# ArmDebuger_6-7_Port.net
KiCad netlist of a schematic drawn in Altium Designer
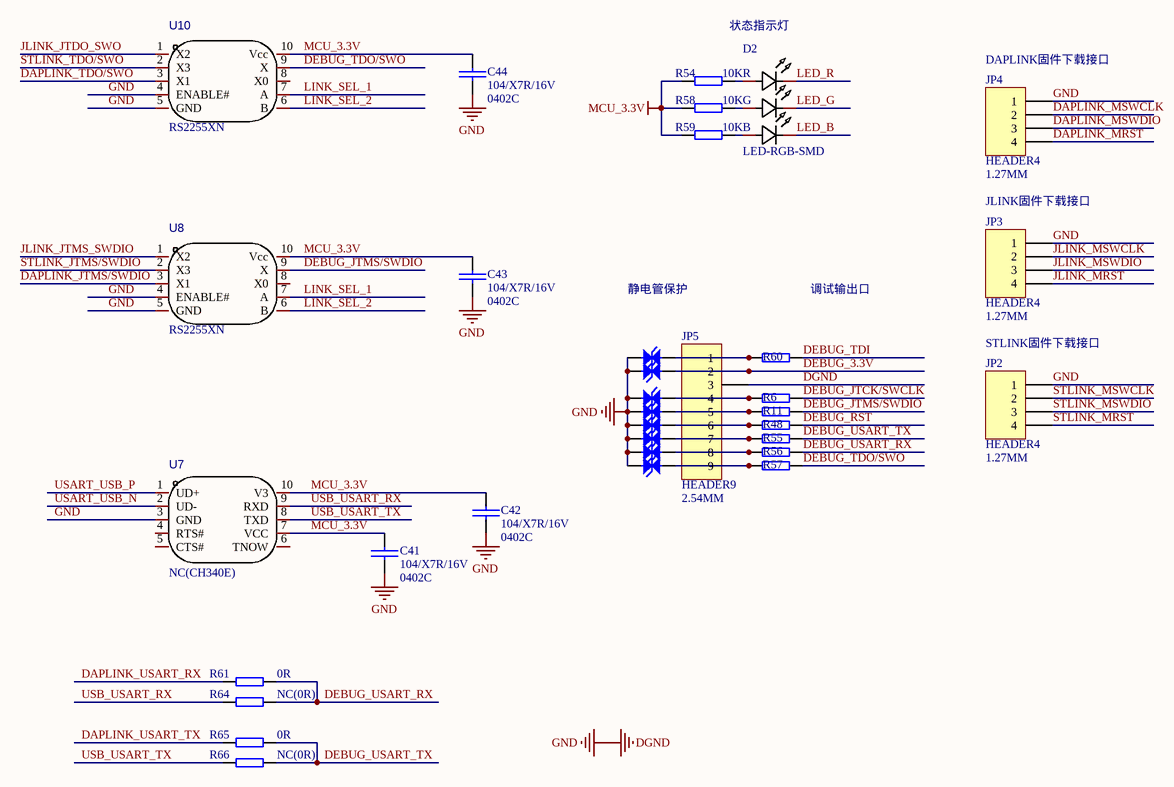
[diagram p0: ArmDebuger(6-7)Port.SchDoc]

(export (version "E")
  (design (tool "Eeschema 10.0.6"))
  (components
    (comp (ref "C41")
      (value "104/X7R/16V")
      (footprint "0402C-SMD-M")
      (fields (field (name "FP") "0402C"))
      (libsource (lib "*") (part "CAP"))
    )
    (comp (ref "C42")
      (value "104/X7R/16V")
      (footprint "0402C-SMD-M")
      (fields (field (name "FP") "0402C"))
      (libsource (lib "*") (part "CAP"))
    )
    (comp (ref "C43")
      (value "104/X7R/16V")
      (footprint "0402C-SMD-M")
      (fields (field (name "FP") "0402C"))
      (libsource (lib "*") (part "CAP"))
    )
    (comp (ref "C44")
      (value "104/X7R/16V")
      (footprint "0402C-SMD-M")
      (fields (field (name "FP") "0402C"))
      (libsource (lib "*") (part "CAP"))
    )
    (comp (ref "D2")
      (value "LED-RGB-SMD")
      (footprint "LED-SMD-6P")
      (libsource (lib "SchLib") (part "LED-RGB-SMD"))
    )
    (comp (ref "ED1")
      (value "KESD3.3V52D-C")
      (footprint "SOD-523")
      (libsource (lib "altium-import") (part "root_2_ESD_"))
    )
    (comp (ref "ED2")
      (value "KESD3.3V52D-C")
      (footprint "SOD-523")
      (libsource (lib "altium-import") (part "root_2_ESD_"))
    )
    (comp (ref "ED3")
      (value "KESD3.3V52D-C")
      (footprint "SOD-523")
      (libsource (lib "altium-import") (part "root_2_ESD_"))
    )
    (comp (ref "ED4")
      (value "KESD3.3V52D-C")
      (footprint "SOD-523")
      (libsource (lib "altium-import") (part "root_2_ESD_"))
    )
    (comp (ref "ED5")
      (value "KESD3.3V52D-C")
      (footprint "SOD-523")
      (libsource (lib "altium-import") (part "root_2_ESD_"))
    )
    (comp (ref "ED6")
      (value "KESD3.3V52D-C")
      (footprint "SOD-523")
      (libsource (lib "altium-import") (part "root_2_ESD_"))
    )
    (comp (ref "ED7")
      (value "KESD3.3V52D-C")
      (footprint "SOD-523")
      (libsource (lib "altium-import") (part "root_2_ESD_"))
    )
    (comp (ref "ED8")
      (value "KESD3.3V52D-C")
      (footprint "SOD-523")
      (libsource (lib "altium-import") (part "root_2_ESD_"))
    )
    (comp (ref "JP2")
      (value "HEADER4")
      (footprint "HDR-1X4-1.27MM")
      (fields (field (name "FP") "1.27MM"))
      (libsource (lib "conm") (part "HEADER4"))
    )
    (comp (ref "JP3")
      (value "HEADER4")
      (footprint "HDR-1X4-1.27MM")
      (fields (field (name "FP") "1.27MM"))
      (libsource (lib "conm") (part "HEADER4"))
    )
    (comp (ref "JP4")
      (value "HEADER4")
      (footprint "HDR-1X4-1.27MM")
      (fields (field (name "FP") "1.27MM"))
      (libsource (lib "conm") (part "HEADER4"))
    )
    (comp (ref "JP5")
      (value "HEADER9")
      (footprint "Header-1x9")
      (fields (field (name "FP") "2.54MM"))
      (libsource (lib "conm") (part "HEADER9"))
    )
    (comp (ref "R6") (value "100R") (footprint "0402R-SMD-M") (libsource (lib "*") (part "RES")))
    (comp (ref "R11") (value "100R") (footprint "0402R-SMD-M") (libsource (lib "*") (part "RES")))
    (comp (ref "R48") (value "100R") (footprint "0402R-SMD-M") (libsource (lib "*") (part "RES")))
    (comp (ref "R54") (value "10K") (footprint "0402R-SMD-M") (libsource (lib "*") (part "RES")))
    (comp (ref "R55") (value "100R") (footprint "0402R-SMD-M") (libsource (lib "*") (part "RES")))
    (comp (ref "R56") (value "100R") (footprint "0402R-SMD-M") (libsource (lib "*") (part "RES")))
    (comp (ref "R57") (value "100R") (footprint "0402R-SMD-M") (libsource (lib "*") (part "RES")))
    (comp (ref "R58") (value "10K") (footprint "0402R-SMD-M") (libsource (lib "*") (part "RES")))
    (comp (ref "R59") (value "10K") (footprint "0402R-SMD-M") (libsource (lib "*") (part "RES")))
    (comp (ref "R60") (value "100R") (footprint "0402R-SMD-M") (libsource (lib "*") (part "RES")))
    (comp (ref "R61") (value "0R") (footprint "0402R-SMD-M") (libsource (lib "*") (part "RES")))
    (comp (ref "R64") (value "NC(0R)") (footprint "0402R-SMD-M") (libsource (lib "*") (part "RES")))
    (comp (ref "R65") (value "0R") (footprint "0402R-SMD-M") (libsource (lib "*") (part "RES")))
    (comp (ref "R66") (value "NC(0R)") (footprint "0402R-SMD-M") (libsource (lib "*") (part "RES")))
    (comp (ref "U7")
      (value "NC(CH340E)")
      (footprint "MSOP-10-L")
      (libsource (lib "altium-import") (part "root_0_CH340E_"))
    )
    (comp (ref "U8")
      (value "RS2255XN")
      (footprint "MSOP-10-L")
      (libsource (lib "altium-import") (part "root_0_RS2255XN_"))
    )
    (comp (ref "U10")
      (value "RS2255XN")
      (footprint "MSOP-10-L")
      (libsource (lib "altium-import") (part "root_0_RS2255XN_"))
    )
  )
  (nets
    (net (code "1") (name "/DAPLINK_JTMS{slash}SWDIO") (class "Default")
      (node (ref "U8") (pin "3") (pinfunction "X1_3") (pintype "passive"))
    )
    (net (code "2") (name "/DAPLINK_MRST") (class "Default")
      (node (ref "JP4") (pin "4") (pinfunction "4_4") (pintype "passive"))
    )
    (net (code "3") (name "/DAPLINK_MSWCLK") (class "Default")
      (node (ref "JP4") (pin "2") (pinfunction "2_2") (pintype "passive"))
    )
    (net (code "4") (name "/DAPLINK_MSWDIO") (class "Default")
      (node (ref "JP4") (pin "3") (pinfunction "3_3") (pintype "passive"))
    )
    (net (code "5") (name "/DAPLINK_TDO{slash}SWO") (class "Default")
      (node (ref "U10") (pin "3") (pinfunction "X1_3") (pintype "passive"))
    )
    (net (code "6") (name "/DAPLINK_USART_RX") (class "Default")
      (node (ref "R61") (pin "2") (pinfunction "2_2") (pintype "passive"))
    )
    (net (code "7") (name "/DAPLINK_USART_TX") (class "Default")
      (node (ref "R65") (pin "2") (pinfunction "2_2") (pintype "passive"))
    )
    (net (code "8") (name "/DEBUG_3.3V") (class "Default")
      (node (ref "ED7") (pin "1") (pinfunction "A_1") (pintype "passive"))
      (node (ref "JP5") (pin "2") (pinfunction "2_2") (pintype "passive"))
    )
    (net (code "9") (name "/DEBUG_JTCK{slash}SWCLK") (class "Default")
      (node (ref "R6") (pin "2") (pinfunction "2_2") (pintype "passive"))
    )
    (net (code "10") (name "/DEBUG_JTMS{slash}SWDIO") (class "Default")
      (node (ref "R11") (pin "2") (pinfunction "2_2") (pintype "passive"))
      (node (ref "U8") (pin "9") (pinfunction "X_9") (pintype "passive"))
    )
    (net (code "11") (name "/DEBUG_RST") (class "Default")
      (node (ref "R48") (pin "2") (pinfunction "2_2") (pintype "passive"))
    )
    (net (code "12") (name "/DEBUG_TDI") (class "Default")
      (node (ref "R60") (pin "2") (pinfunction "2_2") (pintype "passive"))
    )
    (net (code "13") (name "/DEBUG_TDO{slash}SWO") (class "Default")
      (node (ref "R57") (pin "2") (pinfunction "2_2") (pintype "passive"))
      (node (ref "U10") (pin "9") (pinfunction "X_9") (pintype "passive"))
    )
    (net (code "14") (name "/DEBUG_USART_RX") (class "Default")
      (node (ref "R56") (pin "2") (pinfunction "2_2") (pintype "passive"))
      (node (ref "R61") (pin "1") (pinfunction "1_1") (pintype "passive"))
      (node (ref "R64") (pin "1") (pinfunction "1_1") (pintype "passive"))
    )
    (net (code "15") (name "/DEBUG_USART_TX") (class "Default")
      (node (ref "R55") (pin "2") (pinfunction "2_2") (pintype "passive"))
      (node (ref "R65") (pin "1") (pinfunction "1_1") (pintype "passive"))
      (node (ref "R66") (pin "1") (pinfunction "1_1") (pintype "passive"))
    )
    (net (code "16") (name "/JLINK_JTDO_SWO") (class "Default")
      (node (ref "U10") (pin "1") (pinfunction "X2_1") (pintype "passive"))
    )
    (net (code "17") (name "/JLINK_JTMS_SWDIO") (class "Default")
      (node (ref "U8") (pin "1") (pinfunction "X2_1") (pintype "passive"))
    )
    (net (code "18") (name "/JLINK_MRST") (class "Default")
      (node (ref "JP3") (pin "4") (pinfunction "4_4") (pintype "passive"))
    )
    (net (code "19") (name "/JLINK_MSWCLK") (class "Default")
      (node (ref "JP3") (pin "2") (pinfunction "2_2") (pintype "passive"))
    )
    (net (code "20") (name "/JLINK_MSWDIO") (class "Default")
      (node (ref "JP3") (pin "3") (pinfunction "3_3") (pintype "passive"))
    )
    (net (code "21") (name "/LED_B") (class "Default")
      (node (ref "D2") (pin "4") (pinfunction "-_4") (pintype "passive"))
    )
    (net (code "22") (name "/LED_G") (class "Default")
      (node (ref "D2") (pin "5") (pinfunction "-_5") (pintype "passive"))
    )
    (net (code "23") (name "/LED_R") (class "Default")
      (node (ref "D2") (pin "6") (pinfunction "-_6") (pintype "passive"))
    )
    (net (code "24") (name "/LINK_SEL_1") (class "Default")
      (node (ref "U10") (pin "7") (pinfunction "A_7") (pintype "passive"))
      (node (ref "U8") (pin "7") (pinfunction "A_7") (pintype "passive"))
    )
    (net (code "25") (name "/LINK_SEL_2") (class "Default")
      (node (ref "U10") (pin "6") (pinfunction "B_6") (pintype "passive"))
      (node (ref "U8") (pin "6") (pinfunction "B_6") (pintype "passive"))
    )
    (net (code "26") (name "/STLINK_JTMS{slash}SWDIO") (class "Default")
      (node (ref "U8") (pin "2") (pinfunction "X3_2") (pintype "passive"))
    )
    (net (code "27") (name "/STLINK_MRST") (class "Default")
      (node (ref "JP2") (pin "4") (pinfunction "4_4") (pintype "passive"))
    )
    (net (code "28") (name "/STLINK_MSWCLK") (class "Default")
      (node (ref "JP2") (pin "2") (pinfunction "2_2") (pintype "passive"))
    )
    (net (code "29") (name "/STLINK_MSWDIO") (class "Default")
      (node (ref "JP2") (pin "3") (pinfunction "3_3") (pintype "passive"))
    )
    (net (code "30") (name "/STLINK_TDO{slash}SWO") (class "Default")
      (node (ref "U10") (pin "2") (pinfunction "X3_2") (pintype "passive"))
    )
    (net (code "31") (name "/USART_USB_N") (class "Default")
      (node (ref "U7") (pin "2") (pinfunction "UD-_2") (pintype "passive"))
    )
    (net (code "32") (name "/USART_USB_P") (class "Default")
      (node (ref "U7") (pin "1") (pinfunction "UD+_1") (pintype "passive"))
    )
    (net (code "33") (name "/USB_USART_RX") (class "Default")
      (node (ref "R64") (pin "2") (pinfunction "2_2") (pintype "passive"))
      (node (ref "U7") (pin "9") (pinfunction "RXD_9") (pintype "passive"))
    )
    (net (code "34") (name "/USB_USART_TX") (class "Default")
      (node (ref "R66") (pin "2") (pinfunction "2_2") (pintype "passive"))
      (node (ref "U7") (pin "8") (pinfunction "TXD_8") (pintype "passive"))
    )
    (net (code "35") (name "DGND") (class "Default")
      (node (ref "C41") (pin "1") (pinfunction "1_1") (pintype "passive"))
      (node (ref "C42") (pin "1") (pinfunction "1_1") (pintype "passive"))
      (node (ref "C43") (pin "1") (pinfunction "1_1") (pintype "passive"))
      (node (ref "C44") (pin "1") (pinfunction "1_1") (pintype "passive"))
      (node (ref "ED1") (pin "2") (pinfunction "K_2") (pintype "passive"))
      (node (ref "ED2") (pin "2") (pinfunction "K_2") (pintype "passive"))
      (node (ref "ED3") (pin "2") (pinfunction "K_2") (pintype "passive"))
      (node (ref "ED4") (pin "2") (pinfunction "K_2") (pintype "passive"))
      (node (ref "ED5") (pin "2") (pinfunction "K_2") (pintype "passive"))
      (node (ref "ED6") (pin "2") (pinfunction "K_2") (pintype "passive"))
      (node (ref "ED7") (pin "2") (pinfunction "K_2") (pintype "passive"))
      (node (ref "ED8") (pin "2") (pinfunction "K_2") (pintype "passive"))
      (node (ref "JP2") (pin "1") (pinfunction "1_1") (pintype "passive"))
      (node (ref "JP3") (pin "1") (pinfunction "1_1") (pintype "passive"))
      (node (ref "JP4") (pin "1") (pinfunction "1_1") (pintype "passive"))
      (node (ref "JP5") (pin "3") (pinfunction "3_3") (pintype "passive"))
      (node (ref "U10") (pin "4") (pinfunction "ENABLE#_4") (pintype "passive"))
      (node (ref "U10") (pin "5") (pinfunction "GND_5") (pintype "passive"))
      (node (ref "U7") (pin "3") (pinfunction "GND_3") (pintype "passive"))
      (node (ref "U8") (pin "4") (pinfunction "ENABLE#_4") (pintype "passive"))
      (node (ref "U8") (pin "5") (pinfunction "GND_5") (pintype "passive"))
    )
    (net (code "36") (name "MCU_3.3V") (class "Default")
      (node (ref "C41") (pin "2") (pinfunction "1_2") (pintype "passive"))
      (node (ref "C42") (pin "2") (pinfunction "1_2") (pintype "passive"))
      (node (ref "C43") (pin "2") (pinfunction "1_2") (pintype "passive"))
      (node (ref "C44") (pin "2") (pinfunction "1_2") (pintype "passive"))
      (node (ref "R54") (pin "1") (pinfunction "1_1") (pintype "passive"))
      (node (ref "R58") (pin "1") (pinfunction "1_1") (pintype "passive"))
      (node (ref "R59") (pin "1") (pinfunction "1_1") (pintype "passive"))
      (node (ref "U10") (pin "10") (pinfunction "Vcc_10") (pintype "passive"))
      (node (ref "U7") (pin "10") (pinfunction "V3_10") (pintype "passive"))
      (node (ref "U7") (pin "7") (pinfunction "VCC_7") (pintype "passive"))
      (node (ref "U8") (pin "10") (pinfunction "Vcc_10") (pintype "passive"))
    )
    (net (code "37") (name "Net-(D2-B)") (class "Default")
      (node (ref "D2") (pin "3") (pinfunction "B_3") (pintype "passive"))
      (node (ref "R59") (pin "2") (pinfunction "2_2") (pintype "passive"))
    )
    (net (code "38") (name "Net-(D2-G)") (class "Default")
      (node (ref "D2") (pin "2") (pinfunction "G_2") (pintype "passive"))
      (node (ref "R58") (pin "2") (pinfunction "2_2") (pintype "passive"))
    )
    (net (code "39") (name "Net-(D2-R)") (class "Default")
      (node (ref "D2") (pin "1") (pinfunction "R_1") (pintype "passive"))
      (node (ref "R54") (pin "2") (pinfunction "2_2") (pintype "passive"))
    )
    (net (code "40") (name "Net-(ED1-A)") (class "Default")
      (node (ref "ED1") (pin "1") (pinfunction "A_1") (pintype "passive"))
      (node (ref "JP5") (pin "9") (pinfunction "9_9") (pintype "passive"))
      (node (ref "R57") (pin "1") (pinfunction "1_1") (pintype "passive"))
    )
    (net (code "41") (name "Net-(ED2-A)") (class "Default")
      (node (ref "ED2") (pin "1") (pinfunction "A_1") (pintype "passive"))
      (node (ref "JP5") (pin "7") (pinfunction "7_7") (pintype "passive"))
      (node (ref "R55") (pin "1") (pinfunction "1_1") (pintype "passive"))
    )
    (net (code "42") (name "Net-(ED3-A)") (class "Default")
      (node (ref "ED3") (pin "1") (pinfunction "A_1") (pintype "passive"))
      (node (ref "JP5") (pin "5") (pinfunction "5_5") (pintype "passive"))
      (node (ref "R11") (pin "1") (pinfunction "1_1") (pintype "passive"))
    )
    (net (code "43") (name "Net-(ED4-A)") (class "Default")
      (node (ref "ED4") (pin "1") (pinfunction "A_1") (pintype "passive"))
      (node (ref "JP5") (pin "4") (pinfunction "4_4") (pintype "passive"))
      (node (ref "R6") (pin "1") (pinfunction "1_1") (pintype "passive"))
    )
    (net (code "44") (name "Net-(ED5-A)") (class "Default")
      (node (ref "ED5") (pin "1") (pinfunction "A_1") (pintype "passive"))
      (node (ref "JP5") (pin "8") (pinfunction "8_8") (pintype "passive"))
      (node (ref "R56") (pin "1") (pinfunction "1_1") (pintype "passive"))
    )
    (net (code "45") (name "Net-(ED6-A)") (class "Default")
      (node (ref "ED6") (pin "1") (pinfunction "A_1") (pintype "passive"))
      (node (ref "JP5") (pin "6") (pinfunction "6_6") (pintype "passive"))
      (node (ref "R48") (pin "1") (pinfunction "1_1") (pintype "passive"))
    )
    (net (code "46") (name "Net-(ED8-A)") (class "Default")
      (node (ref "ED8") (pin "1") (pinfunction "A_1") (pintype "passive"))
      (node (ref "JP5") (pin "1") (pinfunction "1_1") (pintype "passive"))
      (node (ref "R60") (pin "1") (pinfunction "1_1") (pintype "passive"))
    )
    (net (code "47") (name "unconnected-(U7-CTS#-Pad5)") (class "Default")
      (node (ref "U7") (pin "5") (pinfunction "CTS#_5") (pintype "passive"))
    )
    (net (code "48") (name "unconnected-(U7-RTS#-Pad4)") (class "Default")
      (node (ref "U7") (pin "4") (pinfunction "RTS#_4") (pintype "passive"))
    )
    (net (code "49") (name "unconnected-(U7-TNOW-Pad6)") (class "Default")
      (node (ref "U7") (pin "6") (pinfunction "TNOW_6") (pintype "passive"))
    )
    (net (code "50") (name "unconnected-(U8-X0-Pad8)") (class "Default")
      (node (ref "U8") (pin "8") (pinfunction "X0_8") (pintype "passive"))
    )
    (net (code "51") (name "unconnected-(U10-X0-Pad8)") (class "Default")
      (node (ref "U10") (pin "8") (pinfunction "X0_8") (pintype "passive"))
    )
  )
)
